# mini.net
KiCad netlist of a schematic drawn in EAGLE
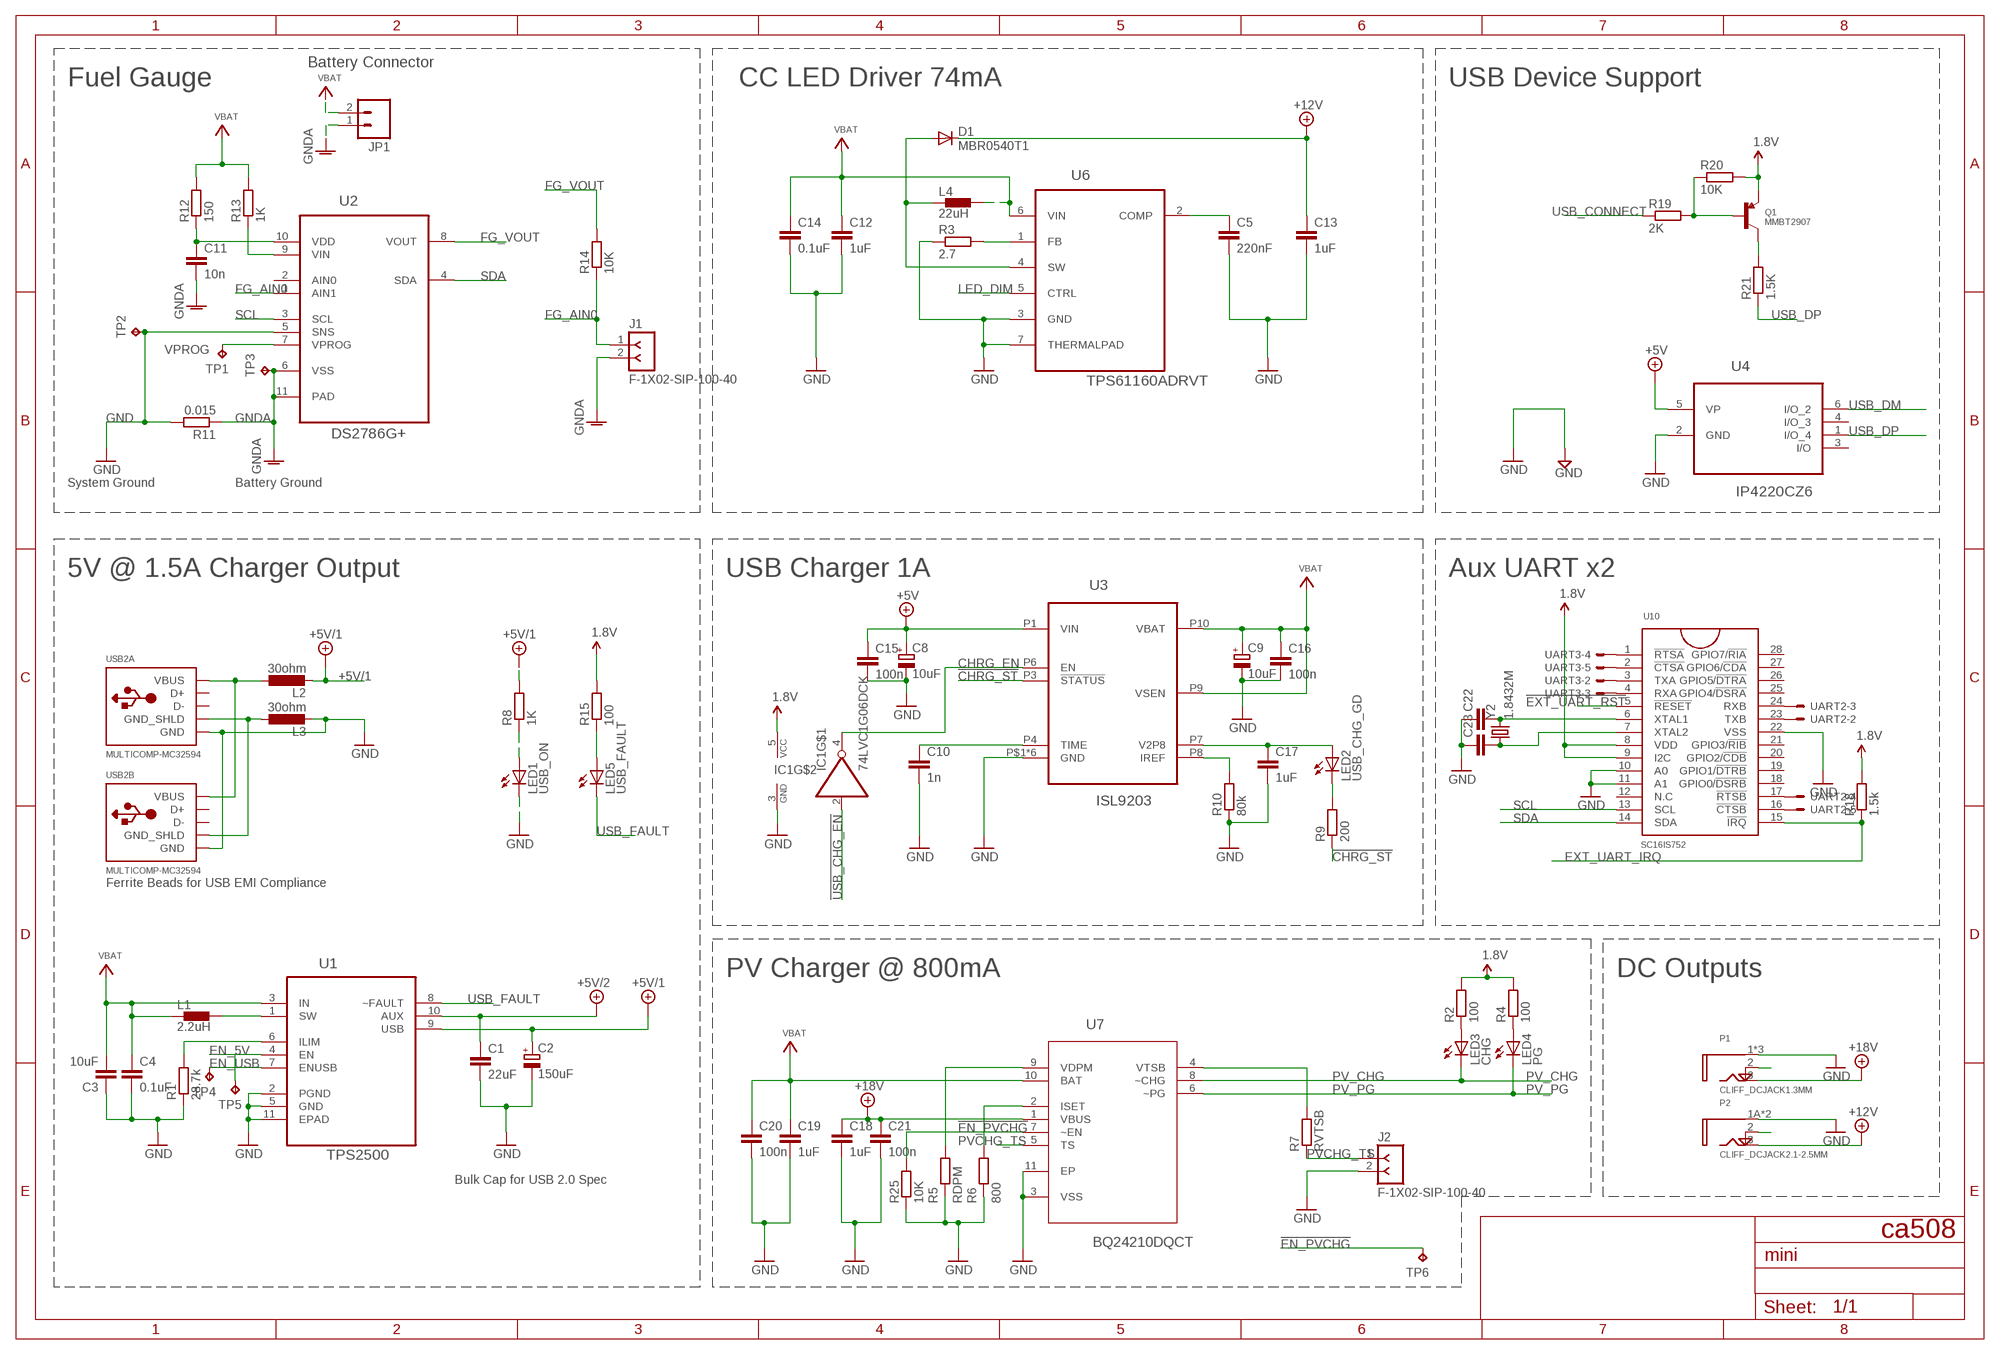
[diagram p0: schematic, sheet 1, part 1 of 2]
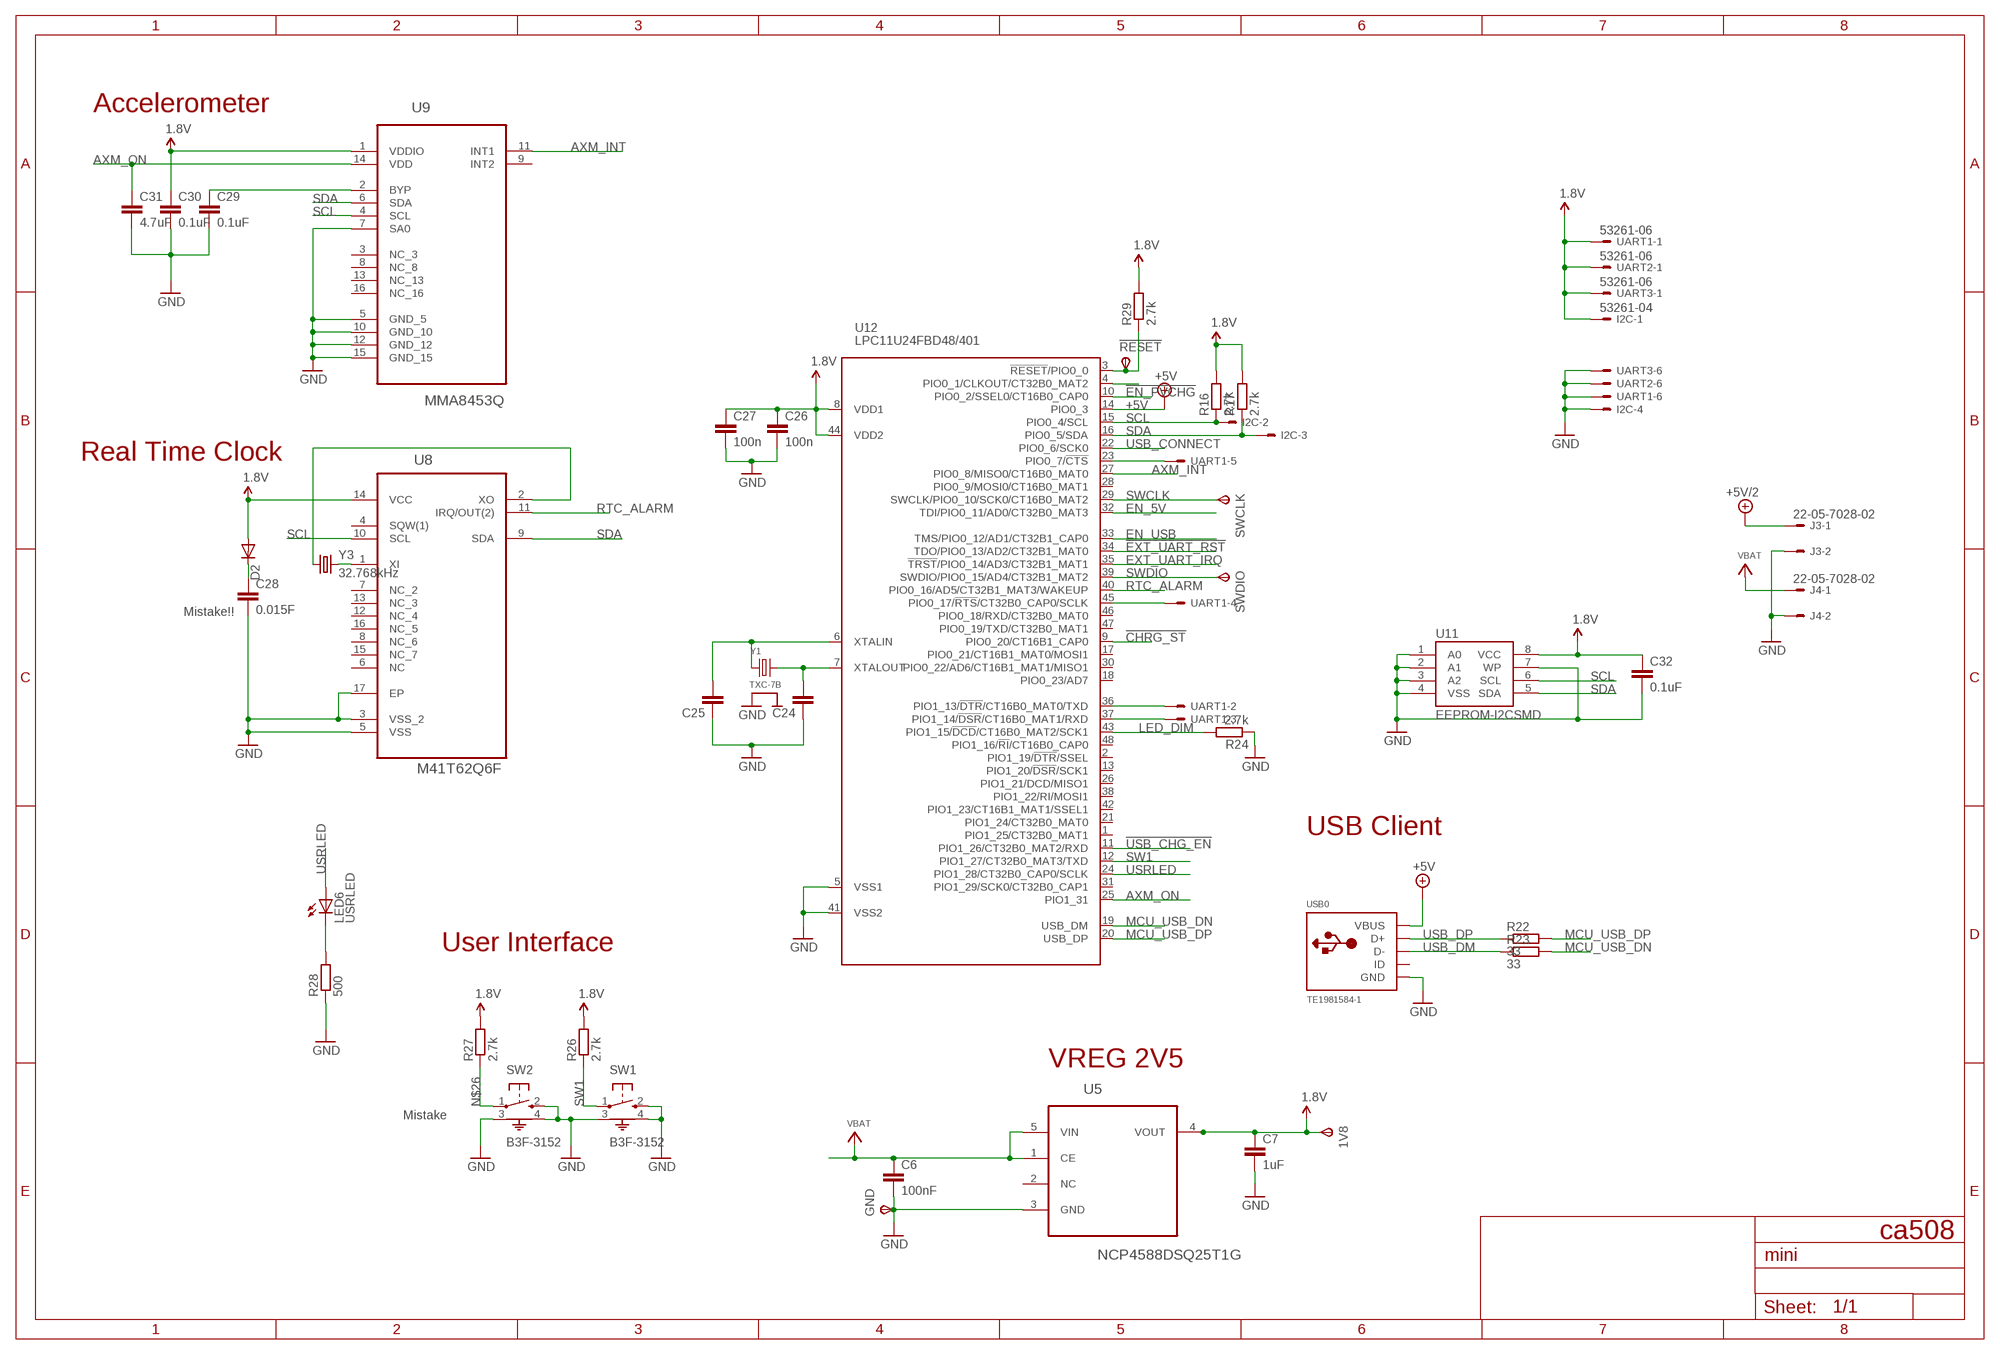
[diagram p1: schematic, sheet 1, part 2 of 2]

(export (version "E")
  (design (tool "Eeschema 10.0.6"))
  (components
    (comp (ref "!RESET!")
      (value "TPSTP13SQ")
      (footprint "eagle-import:TP13SQ")
      (libsource (lib "eagle-import") (part "TPSTP13SQ"))
    )
    (comp (ref "1V8")
      (value "TPSTP13SQ")
      (footprint "eagle-import:TP13SQ")
      (libsource (lib "eagle-import") (part "TPSTP13SQ"))
    )
    (comp (ref "C1")
      (value "22uF")
      (footprint "eagle-import:C1210")
      (libsource (lib "eagle-import") (part "C-EUC1210"))
    )
    (comp (ref "C2")
      (value "150uF")
      (footprint "eagle-import:PANASONIC_D")
      (libsource (lib "eagle-import") (part "CPOL-EUD"))
    )
    (comp (ref "C3")
      (value "10uF")
      (footprint "eagle-import:C0805")
      (libsource (lib "eagle-import") (part "C-EUC0805"))
    )
    (comp (ref "C4")
      (value "0.1uF")
      (footprint "eagle-import:C0603")
      (libsource (lib "eagle-import") (part "C-EUC0603"))
    )
    (comp (ref "C5")
      (value "220nF")
      (footprint "eagle-import:C0603")
      (libsource (lib "eagle-import") (part "C-EUC0603"))
    )
    (comp (ref "C6")
      (value "100nF")
      (footprint "eagle-import:C0805")
      (libsource (lib "eagle-import") (part "C-EUC0805"))
    )
    (comp (ref "C7")
      (value "1uF")
      (footprint "eagle-import:C1206")
      (libsource (lib "eagle-import") (part "C-EUC1206"))
    )
    (comp (ref "C8")
      (value "10uF")
      (footprint "eagle-import:B_3528-21R")
      (libsource (lib "eagle-import") (part "CPOL-EUB/3528-21R"))
    )
    (comp (ref "C9")
      (value "10uF")
      (footprint "eagle-import:B_3528-21R")
      (libsource (lib "eagle-import") (part "CPOL-EUB/3528-21R"))
    )
    (comp (ref "C10")
      (value "1n")
      (footprint "eagle-import:C0603")
      (libsource (lib "eagle-import") (part "C-EUC0603"))
    )
    (comp (ref "C11")
      (value "10n")
      (footprint "eagle-import:C0603")
      (libsource (lib "eagle-import") (part "C-EUC0603"))
    )
    (comp (ref "C12")
      (value "1uF")
      (footprint "eagle-import:C0603")
      (libsource (lib "eagle-import") (part "C-EUC0603"))
    )
    (comp (ref "C13")
      (value "1uF")
      (footprint "eagle-import:C0805")
      (libsource (lib "eagle-import") (part "C-EUC0805"))
    )
    (comp (ref "C14")
      (value "0.1uF")
      (footprint "eagle-import:C0603")
      (libsource (lib "eagle-import") (part "C-EUC0603"))
    )
    (comp (ref "C15")
      (value "100n")
      (footprint "eagle-import:C0603")
      (libsource (lib "eagle-import") (part "C-EUC0603"))
    )
    (comp (ref "C16")
      (value "100n")
      (footprint "eagle-import:C0603")
      (libsource (lib "eagle-import") (part "C-EUC0603"))
    )
    (comp (ref "C17")
      (value "1uF")
      (footprint "eagle-import:C0805")
      (libsource (lib "eagle-import") (part "C-EUC0805"))
    )
    (comp (ref "C18")
      (value "1uF")
      (footprint "eagle-import:C0805")
      (libsource (lib "eagle-import") (part "C-EUC0805"))
    )
    (comp (ref "C19")
      (value "1uF")
      (footprint "eagle-import:C0805")
      (libsource (lib "eagle-import") (part "C-EUC0805"))
    )
    (comp (ref "C20")
      (value "100n")
      (footprint "eagle-import:C0603")
      (libsource (lib "eagle-import") (part "C-EUC0603"))
    )
    (comp (ref "C21")
      (value "100n")
      (footprint "eagle-import:C0603")
      (libsource (lib "eagle-import") (part "C-EUC0603"))
    )
    (comp (ref "C22")
      (value "C-EUC0805")
      (footprint "eagle-import:C0805")
      (libsource (lib "eagle-import") (part "C-EUC0805"))
    )
    (comp (ref "C23")
      (value "C-EUC0805")
      (footprint "eagle-import:C0805")
      (libsource (lib "eagle-import") (part "C-EUC0805"))
    )
    (comp (ref "C24")
      (value "C-EUC0805")
      (footprint "eagle-import:C0805")
      (libsource (lib "eagle-import") (part "C-EUC0805"))
    )
    (comp (ref "C25")
      (value "C-EUC0805")
      (footprint "eagle-import:C0805")
      (libsource (lib "eagle-import") (part "C-EUC0805"))
    )
    (comp (ref "C26")
      (value "100n")
      (footprint "eagle-import:C0603")
      (libsource (lib "eagle-import") (part "C-EUC0603"))
    )
    (comp (ref "C27")
      (value "100n")
      (footprint "eagle-import:C0603")
      (libsource (lib "eagle-import") (part "C-EUC0603"))
    )
    (comp (ref "C28")
      (value "0.015F")
      (footprint "eagle-import:C3225")
      (libsource (lib "eagle-import") (part "C-EUC3225"))
    )
    (comp (ref "C29")
      (value "0.1uF")
      (footprint "eagle-import:C0603")
      (libsource (lib "eagle-import") (part "C-EUC0603"))
    )
    (comp (ref "C30")
      (value "0.1uF")
      (footprint "eagle-import:C0603")
      (libsource (lib "eagle-import") (part "C-EUC0603"))
    )
    (comp (ref "C31")
      (value "4.7uF")
      (footprint "eagle-import:C0805")
      (libsource (lib "eagle-import") (part "C-EUC0805"))
    )
    (comp (ref "C32")
      (value "0.1uF")
      (footprint "eagle-import:C0603")
      (libsource (lib "eagle-import") (part "C-EUC0603"))
    )
    (comp (ref "D1")
      (value "MBR0540T1")
      (footprint "eagle-import:SOD123")
      (libsource (lib "eagle-import") (part "MBR0520LT"))
    )
    (comp (ref "D2")
      (value "DIODE-SOD123")
      (footprint "eagle-import:SOD123")
      (libsource (lib "eagle-import") (part "DIODE-SOD123"))
    )
    (comp (ref "GND")
      (value "TPSTP13SQ")
      (footprint "eagle-import:TP13SQ")
      (libsource (lib "eagle-import") (part "TPSTP13SQ"))
    )
    (comp (ref "I2C")
      (value "53261-04")
      (footprint "eagle-import:53261-04")
      (libsource (lib "eagle-import") (part "53?-04261"))
    )
    (comp (ref "IC1")
      (value "74LVC1G06DCK")
      (footprint "eagle-import:SC70-5")
      (libsource (lib "eagle-import") (part "741G06DCKLVC"))
    )
    (comp (ref "J1")
      (value "F-1X02-SIP-100-40")
      (footprint "eagle-import:SIP-100-02-40")
      (libsource (lib "eagle-import") (part "F-1X02-SIP-100-40"))
    )
    (comp (ref "J2")
      (value "F-1X02-SIP-100-40")
      (footprint "eagle-import:SIP-100-02-40")
      (libsource (lib "eagle-import") (part "F-1X02-SIP-100-40"))
    )
    (comp (ref "J3")
      (value "22-05-7028-02")
      (footprint "eagle-import:7395-02")
      (libsource (lib "eagle-import") (part "22-?-0205-7028"))
    )
    (comp (ref "J4")
      (value "22-05-7028-02")
      (footprint "eagle-import:7395-02")
      (libsource (lib "eagle-import") (part "22-?-0205-7028"))
    )
    (comp (ref "JP1")
      (value "M02-JST-2MM-SMT")
      (footprint "eagle-import:JST-2-SMD")
      (libsource (lib "eagle-import") (part "M02-JST-2MM-SMT"))
    )
    (comp (ref "L1")
      (value "2.2uH")
      (footprint "eagle-import:SDR1006")
      (libsource (lib "eagle-import") (part "SDR1006-XXXKL"))
    )
    (comp (ref "L2")
      (value "30ohm")
      (footprint "eagle-import:L3216C")
      (libsource (lib "eagle-import") (part "L-EUL3216C"))
    )
    (comp (ref "L3")
      (value "30ohm")
      (footprint "eagle-import:L3216C")
      (libsource (lib "eagle-import") (part "L-EUL3216C"))
    )
    (comp (ref "L4")
      (value "22uH")
      (footprint "eagle-import:VLCF-SERIES")
      (libsource (lib "eagle-import") (part "VLCF5020-1"))
    )
    (comp (ref "LED1")
      (value "USB_ON")
      (footprint "eagle-import:CHIP-LED0603")
      (libsource (lib "eagle-import") (part "LEDCHIP-LED0603"))
    )
    (comp (ref "LED2")
      (value "USB_CHG_GD")
      (footprint "eagle-import:CHIP-LED0603")
      (libsource (lib "eagle-import") (part "LEDCHIP-LED0603"))
    )
    (comp (ref "LED3")
      (value "CHG")
      (footprint "eagle-import:CHIP-LED0603")
      (libsource (lib "eagle-import") (part "LEDCHIP-LED0603"))
    )
    (comp (ref "LED4")
      (value "PG")
      (footprint "eagle-import:CHIP-LED0603")
      (libsource (lib "eagle-import") (part "LEDCHIP-LED0603"))
    )
    (comp (ref "LED5")
      (value "USB_FAULT")
      (footprint "eagle-import:CHIP-LED0603")
      (libsource (lib "eagle-import") (part "LEDCHIP-LED0603"))
    )
    (comp (ref "LED6")
      (value "USRLED")
      (footprint "eagle-import:CHIP-LED0603")
      (libsource (lib "eagle-import") (part "LEDCHIP-LED0603"))
    )
    (comp (ref "P1")
      (value "CLIFF_DCJACK1.3MM")
      (footprint "eagle-import:FC68145S")
      (libsource (lib "eagle-import") (part "CLIFF_DCJACK1.3MM"))
    )
    (comp (ref "P2")
      (value "CLIFF_DCJACK2.1-2.5MM")
      (footprint "eagle-import:FC6814XS")
      (libsource (lib "eagle-import") (part "CLIFF_DCJACK2.1-2.5MM"))
    )
    (comp (ref "Q1")
      (value "MMBT2907")
      (footprint "eagle-import:SOT23-R")
      (libsource (lib "eagle-import") (part "TRANSISTOR_PNPSOT23-REFLOW"))
    )
    (comp (ref "R1")
      (value "28.7k")
      (footprint "eagle-import:R0805")
      (libsource (lib "eagle-import") (part "R-EU_R0805"))
    )
    (comp (ref "R2")
      (value "100")
      (footprint "eagle-import:R0603")
      (libsource (lib "eagle-import") (part "R-EU_R0603"))
    )
    (comp (ref "R3")
      (value "2.7")
      (footprint "eagle-import:R0603")
      (libsource (lib "eagle-import") (part "R-EU_R0603"))
    )
    (comp (ref "R4")
      (value "100")
      (footprint "eagle-import:R0603")
      (libsource (lib "eagle-import") (part "R-EU_R0603"))
    )
    (comp (ref "R5")
      (value "RDPM")
      (footprint "eagle-import:R0805")
      (libsource (lib "eagle-import") (part "R-EU_R0805"))
    )
    (comp (ref "R6")
      (value "800")
      (footprint "eagle-import:R0805")
      (libsource (lib "eagle-import") (part "R-EU_R0805"))
    )
    (comp (ref "R7")
      (value "RVTSB")
      (footprint "eagle-import:R0805")
      (libsource (lib "eagle-import") (part "R-EU_R0805"))
    )
    (comp (ref "R8")
      (value "1K")
      (footprint "eagle-import:R0603")
      (libsource (lib "eagle-import") (part "R-EU_R0603"))
    )
    (comp (ref "R9")
      (value "200")
      (footprint "eagle-import:R0603")
      (libsource (lib "eagle-import") (part "R-EU_R0603"))
    )
    (comp (ref "R10")
      (value "80k")
      (footprint "eagle-import:R0805")
      (libsource (lib "eagle-import") (part "R-EU_R0805"))
    )
    (comp (ref "R11")
      (value "0.015")
      (footprint "eagle-import:R2512")
      (libsource (lib "eagle-import") (part "R-EU_R2512"))
    )
    (comp (ref "R12")
      (value "150")
      (footprint "eagle-import:R0805")
      (libsource (lib "eagle-import") (part "R-EU_R0805"))
    )
    (comp (ref "R13")
      (value "1K")
      (footprint "eagle-import:R0805")
      (libsource (lib "eagle-import") (part "R-EU_R0805"))
    )
    (comp (ref "R14")
      (value "10K")
      (footprint "eagle-import:R0805")
      (libsource (lib "eagle-import") (part "R-EU_R0805"))
    )
    (comp (ref "R15")
      (value "100")
      (footprint "eagle-import:R0603")
      (libsource (lib "eagle-import") (part "R-EU_R0603"))
    )
    (comp (ref "R16")
      (value "2.7k")
      (footprint "eagle-import:R0603")
      (libsource (lib "eagle-import") (part "R-EU_R0603"))
    )
    (comp (ref "R17")
      (value "2.7k")
      (footprint "eagle-import:R0603")
      (libsource (lib "eagle-import") (part "R-EU_R0603"))
    )
    (comp (ref "R18")
      (value "1.5k")
      (footprint "eagle-import:R0603")
      (libsource (lib "eagle-import") (part "R-EU_R0603"))
    )
    (comp (ref "R19")
      (value "2K")
      (footprint "eagle-import:R0603")
      (libsource (lib "eagle-import") (part "R-EU_R0603"))
    )
    (comp (ref "R20")
      (value "10K")
      (footprint "eagle-import:R0603")
      (libsource (lib "eagle-import") (part "R-EU_R0603"))
    )
    (comp (ref "R21")
      (value "1.5K")
      (footprint "eagle-import:R0603")
      (libsource (lib "eagle-import") (part "R-EU_R0603"))
    )
    (comp (ref "R22")
      (value "33")
      (footprint "eagle-import:R0603")
      (libsource (lib "eagle-import") (part "R-EU_R0603"))
    )
    (comp (ref "R23")
      (value "33")
      (footprint "eagle-import:R0603")
      (libsource (lib "eagle-import") (part "R-EU_R0603"))
    )
    (comp (ref "R24")
      (value "2.7k")
      (footprint "eagle-import:R0603")
      (libsource (lib "eagle-import") (part "R-EU_R0603"))
    )
    (comp (ref "R25")
      (value "10K")
      (footprint "eagle-import:R0603")
      (libsource (lib "eagle-import") (part "R-EU_R0603"))
    )
    (comp (ref "R26")
      (value "2.7k")
      (footprint "eagle-import:R0603")
      (libsource (lib "eagle-import") (part "R-EU_R0603"))
    )
    (comp (ref "R27")
      (value "2.7k")
      (footprint "eagle-import:R0603")
      (libsource (lib "eagle-import") (part "R-EU_R0603"))
    )
    (comp (ref "R28")
      (value "500")
      (footprint "eagle-import:R0603")
      (libsource (lib "eagle-import") (part "R-EU_R0603"))
    )
    (comp (ref "R29")
      (value "2.7k")
      (footprint "eagle-import:R0603")
      (libsource (lib "eagle-import") (part "R-EU_R0603"))
    )
    (comp (ref "SW1")
      (value "B3F-3152")
      (footprint "eagle-import:B3F-315X")
      (libsource (lib "eagle-import") (part "B3F-3152"))
    )
    (comp (ref "SW2")
      (value "B3F-3152")
      (footprint "eagle-import:B3F-315X")
      (libsource (lib "eagle-import") (part "B3F-3152"))
    )
    (comp (ref "SWCLK")
      (value "TPSTP13SQ")
      (footprint "eagle-import:TP13SQ")
      (libsource (lib "eagle-import") (part "TPSTP13SQ"))
    )
    (comp (ref "SWDIO")
      (value "TPSTP13SQ")
      (footprint "eagle-import:TP13SQ")
      (libsource (lib "eagle-import") (part "TPSTP13SQ"))
    )
    (comp (ref "TP1")
      (value "TPTP14R")
      (footprint "eagle-import:TP14R")
      (libsource (lib "eagle-import") (part "TPTP14R"))
    )
    (comp (ref "TP2")
      (value "TPTP07R")
      (footprint "eagle-import:TP07R")
      (libsource (lib "eagle-import") (part "TPTP07R"))
    )
    (comp (ref "TP3")
      (value "TPTP07R")
      (footprint "eagle-import:TP07R")
      (libsource (lib "eagle-import") (part "TPTP07R"))
    )
    (comp (ref "TP4")
      (value "TPTP07R")
      (footprint "eagle-import:TP07R")
      (libsource (lib "eagle-import") (part "TPTP07R"))
    )
    (comp (ref "TP5")
      (value "TPTP07R")
      (footprint "eagle-import:TP07R")
      (libsource (lib "eagle-import") (part "TPTP07R"))
    )
    (comp (ref "TP6")
      (value "TPTP07R")
      (footprint "eagle-import:TP07R")
      (libsource (lib "eagle-import") (part "TPTP07R"))
    )
    (comp (ref "U1")
      (value "TPS2500")
      (footprint "eagle-import:SON50P300X300X100-11N")
      (fields (field (name "MPN") "TPS2500DRCT"))
      (libsource (lib "eagle-import") (part "TPS2500DRCT"))
    )
    (comp (ref "U2")
      (value "DS2786G+")
      (footprint "eagle-import:DFN300X300X80-11N")
      (libsource (lib "eagle-import") (part "DS2786G+"))
    )
    (comp (ref "U3")
      (value "ISL9203")
      (footprint "eagle-import:INTERSIL_DFN_3X3")
      (libsource (lib "eagle-import") (part "ISL9203"))
    )
    (comp (ref "U4")
      (value "IP4220CZ6")
      (footprint "eagle-import:SOT95P275X110-6N")
      (libsource (lib "eagle-import") (part "IP4220CZ6"))
    )
    (comp (ref "U5")
      (value "NCP4588DSQ25T1G")
      (footprint "eagle-import:SOT65P210X110-5N")
      (libsource (lib "eagle-import") (part "NCP4588DSQ25T1G"))
    )
    (comp (ref "U6")
      (value "TPS61160ADRVT")
      (footprint "eagle-import:SON65P210X210X80-7N")
      (fields (field (name "OC_FARNELL") "1735594") (field (name "OC_NEWARK") "1735594"))
      (libsource (lib "eagle-import") (part "TPS61160ADRVT"))
    )
    (comp (ref "U7")
      (value "BQ24210DQCT")
      (footprint "eagle-import:SON50P200X300X80-11N")
      (libsource (lib "eagle-import") (part "BQ24210DQCT"))
    )
    (comp (ref "U8")
      (value "M41T62Q6F")
      (footprint "eagle-import:QFN50P300X300X100-17N")
      (libsource (lib "eagle-import") (part "M41T62Q6F"))
    )
    (comp (ref "U9")
      (value "MMA8453Q")
      (footprint "eagle-import:QFN50P300X300X100-16N")
      (libsource (lib "eagle-import") (part "MMA8453Q"))
    )
    (comp (ref "U10")
      (value "SC16IS752")
      (footprint "eagle-import:TSSOP28")
      (libsource (lib "eagle-import") (part "SC16IS752"))
    )
    (comp (ref "U11")
      (value "EEPROM-I2CSMD")
      (footprint "eagle-import:SO08")
      (libsource (lib "eagle-import") (part "EEPROM-I2CSMD"))
    )
    (comp (ref "U12")
      (value "LPC11U24FBD48/401")
      (footprint "eagle-import:LQFP48")
      (libsource (lib "eagle-import") (part "LPC11U24FBD48/401"))
    )
    (comp (ref "UART1")
      (value "53261-06")
      (footprint "eagle-import:53261-06")
      (libsource (lib "eagle-import") (part "53?-06261"))
    )
    (comp (ref "UART2")
      (value "53261-06")
      (footprint "eagle-import:53261-06")
      (libsource (lib "eagle-import") (part "53?-06261"))
    )
    (comp (ref "UART3")
      (value "53261-06")
      (footprint "eagle-import:53261-06")
      (libsource (lib "eagle-import") (part "53?-06261"))
    )
    (comp (ref "USB0")
      (value "TE1981584-1")
      (footprint "eagle-import:TE-MICROUSB-AB")
      (libsource (lib "eagle-import") (part "TE1981584-1"))
    )
    (comp (ref "USB2")
      (value "MULTICOMP-MC32594")
      (footprint "eagle-import:MC32594")
      (libsource (lib "eagle-import") (part "MULTICOMP-MC32594"))
    )
    (comp (ref "Y1")
      (value "TXC-7B")
      (footprint "eagle-import:TXC-7B")
      (libsource (lib "eagle-import") (part "TXC-7B"))
    )
    (comp (ref "Y2")
      (value "1.8432M")
      (footprint "eagle-import:HC49U-V")
      (libsource (lib "eagle-import") (part "CRYSTALHC49UV"))
    )
    (comp (ref "Y3")
      (value "32.768kHz")
      (footprint "eagle-import:CRYSTAL-32KHZ-SMD")
      (libsource (lib "eagle-import") (part "CRYSTAL32-SMD"))
    )
  )
  (nets
    (net (code "1") (name "+5V") (class "Default")
      (node (ref "C15") (pin "1") (pinfunction "1_1") (pintype "passive"))
      (node (ref "C8") (pin "+") (pinfunction "+_+") (pintype "passive"))
      (node (ref "U12") (pin "14") (pinfunction "PIO0_3_14") (pintype "bidirectional"))
      (node (ref "U3") (pin "P1") (pinfunction "VIN_P1") (pintype "power_in"))
      (node (ref "U4") (pin "5") (pinfunction "VP_5") (pintype "power_in"))
      (node (ref "USB0") (pin "P1") (pinfunction "VBUS_P1") (pintype "power_in"))
    )
    (net (code "2") (name "+5V{slash}1") (class "Default")
      (node (ref "C2") (pin "+") (pinfunction "+_+") (pintype "passive"))
      (node (ref "L2") (pin "2") (pinfunction "2_2") (pintype "passive"))
      (node (ref "R8") (pin "2") (pinfunction "2_2") (pintype "passive"))
      (node (ref "U1") (pin "9") (pinfunction "USB_9") (pintype "output"))
    )
    (net (code "3") (name "+5V{slash}2") (class "Default")
      (node (ref "C1") (pin "1") (pinfunction "1_1") (pintype "passive"))
      (node (ref "J3") (pin "1") (pinfunction "S_1") (pintype "passive"))
      (node (ref "U1") (pin "10") (pinfunction "AUX_10") (pintype "output"))
    )
    (net (code "4") (name "+12V") (class "Default")
      (node (ref "C13") (pin "1") (pinfunction "1_1") (pintype "passive"))
      (node (ref "D1") (pin "C") (pinfunction "C_C") (pintype "passive"))
      (node (ref "P2") (pin "3") (pinfunction "TIP_3") (pintype "power_in"))
    )
    (net (code "5") (name "+18V") (class "Default")
      (node (ref "C18") (pin "1") (pinfunction "1_1") (pintype "passive"))
      (node (ref "C21") (pin "1") (pinfunction "1_1") (pintype "passive"))
      (node (ref "P1") (pin "3") (pinfunction "TIP_3") (pintype "power_in"))
      (node (ref "U7") (pin "1") (pinfunction "VBUS_1") (pintype "bidirectional"))
    )
    (net (code "6") (name "/AXM_INT") (class "Default")
      (node (ref "U12") (pin "27") (pinfunction "PIO0_8/MISO0/CT16B0_MAT0_27") (pintype "bidirectional"))
      (node (ref "U9") (pin "11") (pinfunction "INT1_11") (pintype "output"))
    )
    (net (code "7") (name "/AXM_ON") (class "Default")
      (node (ref "C31") (pin "1") (pinfunction "1_1") (pintype "passive"))
      (node (ref "U12") (pin "25") (pinfunction "PIO1_31_25") (pintype "bidirectional"))
      (node (ref "U9") (pin "14") (pinfunction "VDD_14") (pintype "power_in"))
    )
    (net (code "8") (name "/CHRG_EN") (class "Default")
      (node (ref "IC1") (pin "4") (pinfunction "O_4") (pintype "open_collector"))
      (node (ref "U3") (pin "P6") (pinfunction "EN_P6") (pintype "input"))
    )
    (net (code "9") (name "/EN_5V") (class "Default")
      (node (ref "TP5") (pin "TP") (pinfunction "TP_TP") (pintype "input"))
      (node (ref "U1") (pin "4") (pinfunction "EN_4") (pintype "input"))
      (node (ref "U12") (pin "32") (pinfunction "TDI/PIO0_11/AD0/CT32B0_MAT3_32") (pintype "bidirectional"))
    )
    (net (code "10") (name "/EN_USB") (class "Default")
      (node (ref "TP4") (pin "TP") (pinfunction "TP_TP") (pintype "input"))
      (node (ref "U1") (pin "7") (pinfunction "ENUSB_7") (pintype "input"))
      (node (ref "U12") (pin "33") (pinfunction "TMS/PIO0_12/AD1/CT32B1_CAP0_33") (pintype "bidirectional"))
    )
    (net (code "11") (name "/EXT_UART_IRQ") (class "Default")
      (node (ref "R18") (pin "1") (pinfunction "1_1") (pintype "passive"))
      (node (ref "U10") (pin "15") (pinfunction "~{IRQ}_15") (pintype "bidirectional"))
      (node (ref "U12") (pin "35") (pinfunction "~{TRST}/PIO0_14/AD3/CT32B1_MAT1_35") (pintype "bidirectional"))
    )
    (net (code "12") (name "/FG_AIN0") (class "Default")
      (node (ref "J1") (pin "1") (pinfunction "1_1") (pintype "passive"))
      (node (ref "R14") (pin "1") (pinfunction "1_1") (pintype "passive"))
      (node (ref "U2") (pin "1") (pinfunction "AIN1_1") (pintype "input"))
    )
    (net (code "13") (name "/FG_VOUT") (class "Default")
      (node (ref "R14") (pin "2") (pinfunction "2_2") (pintype "passive"))
      (node (ref "U2") (pin "8") (pinfunction "VOUT_8") (pintype "output"))
    )
    (net (code "14") (name "/LED_DIM") (class "Default")
      (node (ref "R24") (pin "2") (pinfunction "2_2") (pintype "passive"))
      (node (ref "U12") (pin "43") (pinfunction "PIO1_15/~{DCD}/CT16B0_MAT2/SCK1_43") (pintype "bidirectional"))
      (node (ref "U6") (pin "5") (pinfunction "CTRL_5") (pintype "input"))
    )
    (net (code "15") (name "/MCU_USB_DN") (class "Default")
      (node (ref "R23") (pin "2") (pinfunction "2_2") (pintype "passive"))
      (node (ref "U12") (pin "19") (pinfunction "USB_DM_19") (pintype "bidirectional"))
    )
    (net (code "16") (name "/MCU_USB_DP") (class "Default")
      (node (ref "R22") (pin "2") (pinfunction "2_2") (pintype "passive"))
      (node (ref "U12") (pin "20") (pinfunction "USB_DP_20") (pintype "bidirectional"))
    )
    (net (code "17") (name "/N$26") (class "Default")
      (node (ref "R27") (pin "1") (pinfunction "1_1") (pintype "passive"))
      (node (ref "SW2") (pin "1") (pinfunction "1_1") (pintype "passive"))
    )
    (net (code "18") (name "/PVCHG_TS") (class "Default")
      (node (ref "J2") (pin "1") (pinfunction "1_1") (pintype "passive"))
      (node (ref "R7") (pin "1") (pinfunction "1_1") (pintype "passive"))
      (node (ref "U7") (pin "5") (pinfunction "TS_5") (pintype "input"))
    )
    (net (code "19") (name "/PV_CHG") (class "Default")
      (node (ref "LED3") (pin "C") (pinfunction "C_C") (pintype "passive"))
      (node (ref "U7") (pin "8") (pinfunction "~{CHG}_8") (pintype "output"))
    )
    (net (code "20") (name "/PV_PG") (class "Default")
      (node (ref "LED4") (pin "C") (pinfunction "C_C") (pintype "passive"))
      (node (ref "U7") (pin "6") (pinfunction "~{PG}_6") (pintype "output"))
    )
    (net (code "21") (name "/RTC_ALARM") (class "Default")
      (node (ref "U12") (pin "40") (pinfunction "PIO0_16/AD5/CT32B1_MAT3/WAKEUP_40") (pintype "bidirectional"))
      (node (ref "U8") (pin "11") (pinfunction "IRQ/OUT(2)_11") (pintype "output"))
    )
    (net (code "22") (name "/SCL") (class "Default")
      (node (ref "I2C") (pin "2") (pinfunction "S_2") (pintype "passive"))
      (node (ref "R16") (pin "1") (pinfunction "1_1") (pintype "passive"))
      (node (ref "U10") (pin "13") (pinfunction "SCL_13") (pintype "bidirectional"))
      (node (ref "U11") (pin "6") (pinfunction "SCL_6") (pintype "bidirectional"))
      (node (ref "U12") (pin "15") (pinfunction "PIO0_4/SCL_15") (pintype "bidirectional"))
      (node (ref "U2") (pin "3") (pinfunction "SCL_3") (pintype "input"))
      (node (ref "U8") (pin "10") (pinfunction "SCL_10") (pintype "input"))
      (node (ref "U9") (pin "4") (pinfunction "SCL_4") (pintype "input"))
    )
    (net (code "23") (name "/SDA") (class "Default")
      (node (ref "I2C") (pin "3") (pinfunction "S_3") (pintype "passive"))
      (node (ref "R17") (pin "1") (pinfunction "1_1") (pintype "passive"))
      (node (ref "U10") (pin "14") (pinfunction "SDA_14") (pintype "bidirectional"))
      (node (ref "U11") (pin "5") (pinfunction "SDA_5") (pintype "bidirectional"))
      (node (ref "U12") (pin "16") (pinfunction "PIO0_5/SDA_16") (pintype "bidirectional"))
      (node (ref "U2") (pin "4") (pinfunction "SDA_4") (pintype "output"))
      (node (ref "U8") (pin "9") (pinfunction "SDA_9") (pintype "bidirectional"))
      (node (ref "U9") (pin "6") (pinfunction "SDA_6") (pintype "bidirectional"))
    )
    (net (code "24") (name "/SW1") (class "Default")
      (node (ref "R26") (pin "1") (pinfunction "1_1") (pintype "passive"))
      (node (ref "SW1") (pin "1") (pinfunction "1_1") (pintype "passive"))
      (node (ref "U12") (pin "12") (pinfunction "PIO1_27/CT32B0_MAT3/TXD_12") (pintype "bidirectional"))
    )
    (net (code "25") (name "/SWCLK") (class "Default")
      (node (ref "SWCLK") (pin "TP") (pinfunction "PP_TP") (pintype "input"))
      (node (ref "U12") (pin "29") (pinfunction "SWCLK/PIO0_10/SCK0/CT16B0_MAT2_29") (pintype "bidirectional"))
    )
    (net (code "26") (name "/SWDIO") (class "Default")
      (node (ref "SWDIO") (pin "TP") (pinfunction "PP_TP") (pintype "input"))
      (node (ref "U12") (pin "39") (pinfunction "SWDIO/PIO0_15/AD4/CT32B1_MAT2_39") (pintype "bidirectional"))
    )
    (net (code "27") (name "/USB_CONNECT") (class "Default")
      (node (ref "R19") (pin "1") (pinfunction "1_1") (pintype "passive"))
      (node (ref "U12") (pin "22") (pinfunction "PIO0_6/SCK0_22") (pintype "bidirectional"))
    )
    (net (code "28") (name "/USB_DM") (class "Default")
      (node (ref "R23") (pin "1") (pinfunction "1_1") (pintype "passive"))
      (node (ref "U4") (pin "6") (pinfunction "I/O_2_6") (pintype "bidirectional"))
      (node (ref "USB0") (pin "P2") (pinfunction "D-_P2") (pintype "bidirectional"))
    )
    (net (code "29") (name "/USB_DP") (class "Default")
      (node (ref "R21") (pin "1") (pinfunction "1_1") (pintype "passive"))
      (node (ref "R22") (pin "1") (pinfunction "1_1") (pintype "passive"))
      (node (ref "U4") (pin "1") (pinfunction "I/O_4_1") (pintype "bidirectional"))
      (node (ref "USB0") (pin "P3") (pinfunction "D+_P3") (pintype "bidirectional"))
    )
    (net (code "30") (name "/USB_FAULT") (class "Default")
      (node (ref "LED5") (pin "C") (pinfunction "C_C") (pintype "passive"))
      (node (ref "U1") (pin "8") (pinfunction "~{FAULT}_8") (pintype "output"))
    )
    (net (code "31") (name "/USRLED") (class "Default")
      (node (ref "LED6") (pin "A") (pinfunction "A_A") (pintype "passive"))
      (node (ref "U12") (pin "24") (pinfunction "PIO1_28/CT32B0_CAP0/SCLK_24") (pintype "bidirectional"))
    )
    (net (code "32") (name "/VPROG") (class "Default")
      (node (ref "TP1") (pin "TP") (pinfunction "TP_TP") (pintype "input"))
      (node (ref "U2") (pin "7") (pinfunction "VPROG_7") (pintype "power_in"))
    )
    (net (code "33") (name "/~{CHRG_ST}") (class "Default")
      (node (ref "R9") (pin "1") (pinfunction "1_1") (pintype "passive"))
      (node (ref "U12") (pin "9") (pinfunction "PIO0_20/CT16B1_CAP0_9") (pintype "bidirectional"))
      (node (ref "U3") (pin "P3") (pinfunction "~{STATUS}_P3") (pintype "output"))
    )
    (net (code "34") (name "/~{EN_PVCHG}") (class "Default")
      (node (ref "R25") (pin "2") (pinfunction "2_2") (pintype "passive"))
      (node (ref "TP6") (pin "TP") (pinfunction "TP_TP") (pintype "input"))
      (node (ref "U12") (pin "10") (pinfunction "PIO0_2/SSEL0/CT16B0_CAP0_10") (pintype "bidirectional"))
      (node (ref "U7") (pin "7") (pinfunction "~{EN}_7") (pintype "input"))
    )
    (net (code "35") (name "/~{EXT_UART_RST}") (class "Default")
      (node (ref "U10") (pin "5") (pinfunction "~{RESET}_5") (pintype "bidirectional"))
      (node (ref "U12") (pin "34") (pinfunction "TDO/PIO0_13/AD2/CT32B1_MAT0_34") (pintype "bidirectional"))
    )
    (net (code "36") (name "/~{USB_CHG_EN}") (class "Default")
      (node (ref "IC1") (pin "2") (pinfunction "I_2") (pintype "input"))
      (node (ref "U12") (pin "11") (pinfunction "PIO1_26/CT32B0_MAT2/RXD_11") (pintype "bidirectional"))
    )
    (net (code "37") (name "1.8V") (class "Default")
      (node (ref "1V8") (pin "TP") (pinfunction "PP_TP") (pintype "input"))
      (node (ref "C26") (pin "1") (pinfunction "1_1") (pintype "passive"))
      (node (ref "C27") (pin "1") (pinfunction "1_1") (pintype "passive"))
      (node (ref "C30") (pin "1") (pinfunction "1_1") (pintype "passive"))
      (node (ref "C32") (pin "1") (pinfunction "1_1") (pintype "passive"))
      (node (ref "C7") (pin "1") (pinfunction "1_1") (pintype "passive"))
      (node (ref "D2") (pin "A") (pinfunction "A_A") (pintype "passive"))
      (node (ref "I2C") (pin "1") (pinfunction "S_1") (pintype "passive"))
      (node (ref "IC1") (pin "5") (pinfunction "VCC_5") (pintype "power_in"))
      (node (ref "Q1") (pin "2") (pinfunction "E_2") (pintype "passive"))
      (node (ref "R15") (pin "2") (pinfunction "2_2") (pintype "passive"))
      (node (ref "R16") (pin "2") (pinfunction "2_2") (pintype "passive"))
      (node (ref "R17") (pin "2") (pinfunction "2_2") (pintype "passive"))
      (node (ref "R18") (pin "2") (pinfunction "2_2") (pintype "passive"))
      (node (ref "R2") (pin "2") (pinfunction "2_2") (pintype "passive"))
      (node (ref "R20") (pin "2") (pinfunction "2_2") (pintype "passive"))
      (node (ref "R26") (pin "2") (pinfunction "2_2") (pintype "passive"))
      (node (ref "R27") (pin "2") (pinfunction "2_2") (pintype "passive"))
      (node (ref "R29") (pin "2") (pinfunction "2_2") (pintype "passive"))
      (node (ref "R4") (pin "2") (pinfunction "2_2") (pintype "passive"))
      (node (ref "U10") (pin "8") (pinfunction "VDD_8") (pintype "bidirectional"))
      (node (ref "U10") (pin "9") (pinfunction "I2C_9") (pintype "bidirectional"))
      (node (ref "U11") (pin "8") (pinfunction "VCC_8") (pintype "power_in"))
      (node (ref "U12") (pin "44") (pinfunction "VDD2_44") (pintype "power_in"))
      (node (ref "U12") (pin "8") (pinfunction "VDD1_8") (pintype "power_in"))
      (node (ref "U5") (pin "4") (pinfunction "VOUT_4") (pintype "output"))
      (node (ref "U8") (pin "14") (pinfunction "VCC_14") (pintype "power_in"))
      (node (ref "U9") (pin "1") (pinfunction "VDDIO_1") (pintype "power_in"))
      (node (ref "UART1") (pin "1") (pinfunction "S_1") (pintype "passive"))
      (node (ref "UART2") (pin "1") (pinfunction "S_1") (pintype "passive"))
      (node (ref "UART3") (pin "1") (pinfunction "S_1") (pintype "passive"))
    )
    (net (code "38") (name "GND") (class "Default")
      (node (ref "C1") (pin "2") (pinfunction "2_2") (pintype "passive"))
      (node (ref "C10") (pin "2") (pinfunction "2_2") (pintype "passive"))
      (node (ref "C12") (pin "2") (pinfunction "2_2") (pintype "passive"))
      (node (ref "C13") (pin "2") (pinfunction "2_2") (pintype "passive"))
      (node (ref "C14") (pin "2") (pinfunction "2_2") (pintype "passive"))
      (node (ref "C15") (pin "2") (pinfunction "2_2") (pintype "passive"))
      (node (ref "C16") (pin "2") (pinfunction "2_2") (pintype "passive"))
      (node (ref "C17") (pin "2") (pinfunction "2_2") (pintype "passive"))
      (node (ref "C18") (pin "2") (pinfunction "2_2") (pintype "passive"))
      (node (ref "C19") (pin "2") (pinfunction "2_2") (pintype "passive"))
      (node (ref "C2") (pin "-") (pinfunction "-_-") (pintype "passive"))
      (node (ref "C20") (pin "2") (pinfunction "2_2") (pintype "passive"))
      (node (ref "C21") (pin "2") (pinfunction "2_2") (pintype "passive"))
      (node (ref "C22") (pin "1") (pinfunction "1_1") (pintype "passive"))
      (node (ref "C23") (pin "1") (pinfunction "1_1") (pintype "passive"))
      (node (ref "C24") (pin "1") (pinfunction "1_1") (pintype "passive"))
      (node (ref "C25") (pin "1") (pinfunction "1_1") (pintype "passive"))
      (node (ref "C26") (pin "2") (pinfunction "2_2") (pintype "passive"))
      (node (ref "C27") (pin "2") (pinfunction "2_2") (pintype "passive"))
      (node (ref "C28") (pin "2") (pinfunction "2_2") (pintype "passive"))
      (node (ref "C29") (pin "2") (pinfunction "2_2") (pintype "passive"))
      (node (ref "C3") (pin "1") (pinfunction "1_1") (pintype "passive"))
      (node (ref "C30") (pin "2") (pinfunction "2_2") (pintype "passive"))
      (node (ref "C31") (pin "2") (pinfunction "2_2") (pintype "passive"))
      (node (ref "C32") (pin "2") (pinfunction "2_2") (pintype "passive"))
      (node (ref "C4") (pin "2") (pinfunction "2_2") (pintype "passive"))
      (node (ref "C5") (pin "2") (pinfunction "2_2") (pintype "passive"))
      (node (ref "C6") (pin "2") (pinfunction "2_2") (pintype "passive"))
      (node (ref "C7") (pin "2") (pinfunction "2_2") (pintype "passive"))
      (node (ref "C8") (pin "-") (pinfunction "-_-") (pintype "passive"))
      (node (ref "C9") (pin "-") (pinfunction "-_-") (pintype "passive"))
      (node (ref "GND") (pin "TP") (pinfunction "PP_TP") (pintype "input"))
      (node (ref "I2C") (pin "4") (pinfunction "S_4") (pintype "passive"))
      (node (ref "IC1") (pin "3") (pinfunction "GND_3") (pintype "power_in"))
      (node (ref "J2") (pin "2") (pinfunction "2_2") (pintype "passive"))
      (node (ref "J3") (pin "2") (pinfunction "S_2") (pintype "passive"))
      (node (ref "J4") (pin "2") (pinfunction "S_2") (pintype "passive"))
      (node (ref "L3") (pin "2") (pinfunction "2_2") (pintype "passive"))
      (node (ref "LED1") (pin "C") (pinfunction "C_C") (pintype "passive"))
      (node (ref "P1") (pin "1") (pinfunction "SLEEVE_1") (pintype "power_in"))
      (node (ref "P1") (pin "4A") (pinfunction "SLEEVE_4A") (pintype "power_in"))
      (node (ref "P1") (pin "4B") (pinfunction "SLEEVE_4B") (pintype "power_in"))
      (node (ref "P2") (pin "1A") (pinfunction "SLEEVE_1A") (pintype "power_in"))
      (node (ref "P2") (pin "1B") (pinfunction "SLEEVE_1B") (pintype "power_in"))
      (node (ref "R1") (pin "1") (pinfunction "1_1") (pintype "passive"))
      (node (ref "R10") (pin "1") (pinfunction "1_1") (pintype "passive"))
      (node (ref "R11") (pin "2") (pinfunction "2_2") (pintype "passive"))
      (node (ref "R24") (pin "1") (pinfunction "1_1") (pintype "passive"))
      (node (ref "R25") (pin "1") (pinfunction "1_1") (pintype "passive"))
      (node (ref "R28") (pin "1") (pinfunction "1_1") (pintype "passive"))
      (node (ref "R3") (pin "1") (pinfunction "1_1") (pintype "passive"))
      (node (ref "R5") (pin "1") (pinfunction "1_1") (pintype "passive"))
      (node (ref "R6") (pin "1") (pinfunction "1_1") (pintype "passive"))
      (node (ref "SW1") (pin "2") (pinfunction "3_2") (pintype "passive"))
      (node (ref "SW1") (pin "3") (pinfunction "2_3") (pintype "passive"))
      (node (ref "SW1") (pin "4") (pinfunction "4_4") (pintype "passive"))
      (node (ref "SW2") (pin "2") (pinfunction "3_2") (pintype "passive"))
      (node (ref "SW2") (pin "3") (pinfunction "2_3") (pintype "passive"))
      (node (ref "SW2") (pin "4") (pinfunction "4_4") (pintype "passive"))
      (node (ref "TP2") (pin "TP") (pinfunction "TP_TP") (pintype "input"))
      (node (ref "U1") (pin "11") (pinfunction "EPAD_11") (pintype "passive"))
      (node (ref "U1") (pin "2") (pinfunction "PGND_2") (pintype "passive"))
      (node (ref "U1") (pin "5") (pinfunction "GND_5") (pintype "passive"))
      (node (ref "U10") (pin "10") (pinfunction "A0_10") (pintype "input"))
      (node (ref "U10") (pin "11") (pinfunction "A1_11") (pintype "bidirectional"))
      (node (ref "U10") (pin "22") (pinfunction "VSS_22") (pintype "bidirectional"))
      (node (ref "U11") (pin "1") (pinfunction "A0_1") (pintype "bidirectional"))
      (node (ref "U11") (pin "2") (pinfunction "A1_2") (pintype "bidirectional"))
      (node (ref "U11") (pin "3") (pinfunction "A2_3") (pintype "bidirectional"))
      (node (ref "U11") (pin "4") (pinfunction "VSS_4") (pintype "power_in"))
      (node (ref "U11") (pin "7") (pinfunction "WP_7") (pintype "bidirectional"))
      (node (ref "U12") (pin "41") (pinfunction "VSS2_41") (pintype "power_in"))
      (node (ref "U12") (pin "5") (pinfunction "VSS1_5") (pintype "power_in"))
      (node (ref "U2") (pin "5") (pinfunction "SNS_5") (pintype "input"))
      (node (ref "U3") (pin "P$1") (pinfunction "GND_P$1") (pintype "passive"))
      (node (ref "U3") (pin "P$2") (pinfunction "GND_P$2") (pintype "passive"))
      (node (ref "U3") (pin "P$3") (pinfunction "GND_P$3") (pintype "passive"))
      (node (ref "U3") (pin "P$4") (pinfunction "GND_P$4") (pintype "passive"))
      (node (ref "U3") (pin "P5") (pinfunction "GND_P5") (pintype "passive"))
      (node (ref "U3") (pin "PAD") (pinfunction "GND_PAD") (pintype "passive"))
      (node (ref "U4") (pin "2") (pinfunction "GND_2") (pintype "passive"))
      (node (ref "U5") (pin "3") (pinfunction "GND_3") (pintype "passive"))
      (node (ref "U6") (pin "3") (pinfunction "GND_3") (pintype "passive"))
      (node (ref "U6") (pin "7") (pinfunction "THERMALPAD_7") (pintype "passive"))
      (node (ref "U7") (pin "11") (pinfunction "EP_11") (pintype "passive"))
      (node (ref "U7") (pin "3") (pinfunction "VSS_3") (pintype "passive"))
      (node (ref "U8") (pin "17") (pinfunction "EP_17") (pintype "passive"))
      (node (ref "U8") (pin "3") (pinfunction "VSS_2_3") (pintype "passive"))
      (node (ref "U8") (pin "5") (pinfunction "VSS_5") (pintype "passive"))
      (node (ref "U9") (pin "10") (pinfunction "GND_10_10") (pintype "passive"))
      (node (ref "U9") (pin "12") (pinfunction "GND_12_12") (pintype "passive"))
      (node (ref "U9") (pin "15") (pinfunction "GND_15_15") (pintype "passive"))
      (node (ref "U9") (pin "5") (pinfunction "GND_5_5") (pintype "passive"))
      (node (ref "U9") (pin "7") (pinfunction "SA0_7") (pintype "input"))
      (node (ref "UART1") (pin "6") (pinfunction "S_6") (pintype "passive"))
      (node (ref "UART2") (pin "6") (pinfunction "S_6") (pintype "passive"))
      (node (ref "UART3") (pin "6") (pinfunction "S_6") (pintype "passive"))
      (node (ref "USB0") (pin "P5") (pinfunction "GND_P5") (pintype "power_in"))
      (node (ref "USB2") (pin "USB1-4") (pinfunction "GND_USB1-4") (pintype "power_in"))
      (node (ref "USB2") (pin "USB2-4") (pinfunction "GND_USB2-4") (pintype "power_in"))
      (node (ref "Y1") (pin "2") (pinfunction "4_2") (pintype "passive"))
      (node (ref "Y1") (pin "4") (pinfunction "4_4") (pintype "passive"))
    )
    (net (code "39") (name "GNDA") (class "Default")
      (node (ref "C11") (pin "2") (pinfunction "2_2") (pintype "passive"))
      (node (ref "J1") (pin "2") (pinfunction "2_2") (pintype "passive"))
      (node (ref "JP1") (pin "1") (pinfunction "2_1") (pintype "passive"))
      (node (ref "R11") (pin "1") (pinfunction "1_1") (pintype "passive"))
      (node (ref "TP3") (pin "TP") (pinfunction "TP_TP") (pintype "input"))
      (node (ref "U2") (pin "11") (pinfunction "PAD_11") (pintype "passive"))
      (node (ref "U2") (pin "6") (pinfunction "VSS_6") (pintype "passive"))
    )
    (net (code "40") (name "Net-(!RESET!-PP)") (class "Default")
      (node (ref "!RESET!") (pin "TP") (pinfunction "PP_TP") (pintype "input"))
      (node (ref "R29") (pin "1") (pinfunction "1_1") (pintype "passive"))
      (node (ref "U12") (pin "3") (pinfunction "~{RESET}/PIO0_0_3") (pintype "bidirectional"))
    )
    (net (code "41") (name "Net-(C28-Pad1)") (class "Default")
      (node (ref "C28") (pin "1") (pinfunction "1_1") (pintype "passive"))
      (node (ref "D2") (pin "C") (pinfunction "C_C") (pintype "passive"))
    )
    (net (code "42") (name "Net-(L1-2)") (class "Default")
      (node (ref "L1") (pin "P$2") (pinfunction "2_P$2") (pintype "passive"))
      (node (ref "U1") (pin "1") (pinfunction "SW_1") (pintype "power_in"))
    )
    (net (code "43") (name "Net-(L3-Pad1)") (class "Default")
      (node (ref "L3") (pin "1") (pinfunction "1_1") (pintype "passive"))
      (node (ref "USB2") (pin "P$1") (pinfunction "GND_SHLD_P$1") (pintype "power_in"))
      (node (ref "USB2") (pin "P$2") (pinfunction "GND_SHLD_P$2") (pintype "power_in"))
      (node (ref "USB2") (pin "P$3") (pinfunction "GND_SHLD_P$3") (pintype "power_in"))
      (node (ref "USB2") (pin "P$4") (pinfunction "GND_SHLD_P$4") (pintype "power_in"))
    )
    (net (code "44") (name "Net-(LED1-PadA)") (class "Default")
      (node (ref "LED1") (pin "A") (pinfunction "A_A") (pintype "passive"))
      (node (ref "R8") (pin "1") (pinfunction "1_1") (pintype "passive"))
    )
    (net (code "45") (name "Net-(LED2-PadC)") (class "Default")
      (node (ref "LED2") (pin "C") (pinfunction "C_C") (pintype "passive"))
      (node (ref "R9") (pin "2") (pinfunction "2_2") (pintype "passive"))
    )
    (net (code "46") (name "Net-(LED3-PadA)") (class "Default")
      (node (ref "LED3") (pin "A") (pinfunction "A_A") (pintype "passive"))
      (node (ref "R2") (pin "1") (pinfunction "1_1") (pintype "passive"))
    )
    (net (code "47") (name "Net-(LED4-PadA)") (class "Default")
      (node (ref "LED4") (pin "A") (pinfunction "A_A") (pintype "passive"))
      (node (ref "R4") (pin "1") (pinfunction "1_1") (pintype "passive"))
    )
    (net (code "48") (name "Net-(LED5-PadA)") (class "Default")
      (node (ref "LED5") (pin "A") (pinfunction "A_A") (pintype "passive"))
      (node (ref "R15") (pin "1") (pinfunction "1_1") (pintype "passive"))
    )
    (net (code "49") (name "Net-(LED6-PadC)") (class "Default")
      (node (ref "LED6") (pin "C") (pinfunction "C_C") (pintype "passive"))
      (node (ref "R28") (pin "2") (pinfunction "2_2") (pintype "passive"))
    )
    (net (code "50") (name "Net-(Q1-B)") (class "Default")
      (node (ref "Q1") (pin "1") (pinfunction "B_1") (pintype "passive"))
      (node (ref "R19") (pin "2") (pinfunction "2_2") (pintype "passive"))
      (node (ref "R20") (pin "1") (pinfunction "1_1") (pintype "passive"))
    )
    (net (code "51") (name "Net-(Q1-C)") (class "Default")
      (node (ref "Q1") (pin "3") (pinfunction "C_3") (pintype "passive"))
      (node (ref "R21") (pin "2") (pinfunction "2_2") (pintype "passive"))
    )
    (net (code "52") (name "Net-(U1-ILIM)") (class "Default")
      (node (ref "R1") (pin "2") (pinfunction "2_2") (pintype "passive"))
      (node (ref "U1") (pin "6") (pinfunction "ILIM_6") (pintype "input"))
    )
    (net (code "53") (name "Net-(U2-VDD)") (class "Default")
      (node (ref "C11") (pin "1") (pinfunction "1_1") (pintype "passive"))
      (node (ref "R12") (pin "1") (pinfunction "1_1") (pintype "passive"))
      (node (ref "U2") (pin "10") (pinfunction "VDD_10") (pintype "power_in"))
    )
    (net (code "54") (name "Net-(U2-VIN)") (class "Default")
      (node (ref "R13") (pin "1") (pinfunction "1_1") (pintype "passive"))
      (node (ref "U2") (pin "9") (pinfunction "VIN_9") (pintype "input"))
    )
    (net (code "55") (name "Net-(U3-IREF)") (class "Default")
      (node (ref "R10") (pin "2") (pinfunction "2_2") (pintype "passive"))
      (node (ref "U3") (pin "P8") (pinfunction "IREF_P8") (pintype "input"))
    )
    (net (code "56") (name "Net-(U3-TIME)") (class "Default")
      (node (ref "C10") (pin "1") (pinfunction "1_1") (pintype "passive"))
      (node (ref "U3") (pin "P4") (pinfunction "TIME_P4") (pintype "input"))
    )
    (net (code "57") (name "Net-(U3-V2P8)") (class "Default")
      (node (ref "C17") (pin "1") (pinfunction "1_1") (pintype "passive"))
      (node (ref "LED2") (pin "A") (pinfunction "A_A") (pintype "passive"))
      (node (ref "U3") (pin "P7") (pinfunction "V2P8_P7") (pintype "output"))
    )
    (net (code "58") (name "Net-(U6-COMP)") (class "Default")
      (node (ref "C5") (pin "1") (pinfunction "1_1") (pintype "passive"))
      (node (ref "U6") (pin "2") (pinfunction "COMP_2") (pintype "output"))
    )
    (net (code "59") (name "Net-(U6-FB)") (class "Default")
      (node (ref "R3") (pin "2") (pinfunction "2_2") (pintype "passive"))
      (node (ref "U6") (pin "1") (pinfunction "FB_1") (pintype "input"))
    )
    (net (code "60") (name "Net-(U6-SW)") (class "Default")
      (node (ref "D1") (pin "A") (pinfunction "A_A") (pintype "passive"))
      (node (ref "L4") (pin "1") (pinfunction "1_1") (pintype "passive"))
      (node (ref "U6") (pin "4") (pinfunction "SW_4") (pintype "input"))
    )
    (net (code "61") (name "Net-(U7-ISET)") (class "Default")
      (node (ref "R6") (pin "2") (pinfunction "2_2") (pintype "passive"))
      (node (ref "U7") (pin "2") (pinfunction "ISET_2") (pintype "input"))
    )
    (net (code "62") (name "Net-(U7-VDPM)") (class "Default")
      (node (ref "R5") (pin "2") (pinfunction "2_2") (pintype "passive"))
      (node (ref "U7") (pin "9") (pinfunction "VDPM_9") (pintype "input"))
    )
    (net (code "63") (name "Net-(U7-VTSB)") (class "Default")
      (node (ref "R7") (pin "2") (pinfunction "2_2") (pintype "passive"))
      (node (ref "U7") (pin "4") (pinfunction "VTSB_4") (pintype "output"))
    )
    (net (code "64") (name "Net-(U8-XI)") (class "Default")
      (node (ref "U8") (pin "1") (pinfunction "XI_1") (pintype "input"))
      (node (ref "Y3") (pin "X2") (pinfunction "2_X2") (pintype "passive"))
    )
    (net (code "65") (name "Net-(U8-XO)") (class "Default")
      (node (ref "U8") (pin "2") (pinfunction "XO_2") (pintype "output"))
      (node (ref "Y3") (pin "X1") (pinfunction "1_X1") (pintype "passive"))
    )
    (net (code "66") (name "Net-(U9-BYP)") (class "Default")
      (node (ref "C29") (pin "1") (pinfunction "1_1") (pintype "passive"))
      (node (ref "U9") (pin "2") (pinfunction "BYP_2") (pintype "input"))
    )
    (net (code "67") (name "Net-(U10-RXA)") (class "Default")
      (node (ref "U10") (pin "4") (pinfunction "RXA_4") (pintype "bidirectional"))
      (node (ref "UART3") (pin "3") (pinfunction "S_3") (pintype "passive"))
    )
    (net (code "68") (name "Net-(U10-RXB)") (class "Default")
      (node (ref "U10") (pin "24") (pinfunction "RXB_24") (pintype "bidirectional"))
      (node (ref "UART2") (pin "3") (pinfunction "S_3") (pintype "passive"))
    )
    (net (code "69") (name "Net-(U10-TXA)") (class "Default")
      (node (ref "U10") (pin "3") (pinfunction "TXA_3") (pintype "input"))
      (node (ref "UART3") (pin "2") (pinfunction "S_2") (pintype "passive"))
    )
    (net (code "70") (name "Net-(U10-TXB)") (class "Default")
      (node (ref "U10") (pin "23") (pinfunction "TXB_23") (pintype "bidirectional"))
      (node (ref "UART2") (pin "2") (pinfunction "S_2") (pintype "passive"))
    )
    (net (code "71") (name "Net-(U10-XTAL1)") (class "Default")
      (node (ref "C22") (pin "2") (pinfunction "2_2") (pintype "passive"))
      (node (ref "U10") (pin "6") (pinfunction "XTAL1_6") (pintype "bidirectional"))
      (node (ref "Y2") (pin "2") (pinfunction "2_2") (pintype "passive"))
    )
    (net (code "72") (name "Net-(U10-XTAL2)") (class "Default")
      (node (ref "C23") (pin "2") (pinfunction "2_2") (pintype "passive"))
      (node (ref "U10") (pin "7") (pinfunction "XTAL2_7") (pintype "bidirectional"))
      (node (ref "Y2") (pin "1") (pinfunction "1_1") (pintype "passive"))
    )
    (net (code "73") (name "Net-(U10-~{CTSA})") (class "Default")
      (node (ref "U10") (pin "2") (pinfunction "~{CTSA}_2") (pintype "input"))
      (node (ref "UART3") (pin "5") (pinfunction "S_5") (pintype "passive"))
    )
    (net (code "74") (name "Net-(U10-~{CTSB})") (class "Default")
      (node (ref "U10") (pin "16") (pinfunction "~{CTSB}_16") (pintype "bidirectional"))
      (node (ref "UART2") (pin "5") (pinfunction "S_5") (pintype "passive"))
    )
    (net (code "75") (name "Net-(U10-~{RTSA})") (class "Default")
      (node (ref "U10") (pin "1") (pinfunction "~{RTSA}_1") (pintype "input"))
      (node (ref "UART3") (pin "4") (pinfunction "S_4") (pintype "passive"))
    )
    (net (code "76") (name "Net-(U10-~{RTSB})") (class "Default")
      (node (ref "U10") (pin "17") (pinfunction "~{RTSB}_17") (pintype "bidirectional"))
      (node (ref "UART2") (pin "4") (pinfunction "S_4") (pintype "passive"))
    )
    (net (code "77") (name "Net-(U12-PIO0_7{slash}~{CTS})") (class "Default")
      (node (ref "U12") (pin "23") (pinfunction "PIO0_7/~{CTS}_23") (pintype "bidirectional"))
      (node (ref "UART1") (pin "5") (pinfunction "S_5") (pintype "passive"))
    )
    (net (code "78") (name "Net-(U12-PIO0_17{slash}~{RTS}{slash}CT32B0_CAP0{slash}SCLK)") (class "Default")
      (node (ref "U12") (pin "45") (pinfunction "PIO0_17/~{RTS}/CT32B0_CAP0/SCLK_45") (pintype "bidirectional"))
      (node (ref "UART1") (pin "4") (pinfunction "S_4") (pintype "passive"))
    )
    (net (code "79") (name "Net-(U12-PIO1_13{slash}~{DTR}{slash}CT16B0_MAT0{slash}TXD)") (class "Default")
      (node (ref "U12") (pin "36") (pinfunction "PIO1_13/~{DTR}/CT16B0_MAT0/TXD_36") (pintype "bidirectional"))
      (node (ref "UART1") (pin "2") (pinfunction "S_2") (pintype "passive"))
    )
    (net (code "80") (name "Net-(U12-PIO1_14{slash}~{DSR}{slash}CT16B0_MAT1{slash}RXD)") (class "Default")
      (node (ref "U12") (pin "37") (pinfunction "PIO1_14/~{DSR}/CT16B0_MAT1/RXD_37") (pintype "bidirectional"))
      (node (ref "UART1") (pin "3") (pinfunction "S_3") (pintype "passive"))
    )
    (net (code "81") (name "Net-(U12-XTALIN)") (class "Default")
      (node (ref "C25") (pin "2") (pinfunction "2_2") (pintype "passive"))
      (node (ref "U12") (pin "6") (pinfunction "XTALIN_6") (pintype "passive"))
      (node (ref "Y1") (pin "1") (pinfunction "1_1") (pintype "passive"))
    )
    (net (code "82") (name "Net-(U12-XTALOUT)") (class "Default")
      (node (ref "C24") (pin "2") (pinfunction "2_2") (pintype "passive"))
      (node (ref "U12") (pin "7") (pinfunction "XTALOUT_7") (pintype "passive"))
      (node (ref "Y1") (pin "3") (pinfunction "2_3") (pintype "passive"))
    )
    (net (code "83") (name "Net-(USB2A-VBUS)") (class "Default")
      (node (ref "L2") (pin "1") (pinfunction "1_1") (pintype "passive"))
      (node (ref "USB2") (pin "USB1-1") (pinfunction "VBUS_USB1-1") (pintype "power_in"))
      (node (ref "USB2") (pin "USB2-1") (pinfunction "VBUS_USB2-1") (pintype "power_in"))
    )
    (net (code "84") (name "VBAT") (class "Default")
      (node (ref "C12") (pin "1") (pinfunction "1_1") (pintype "passive"))
      (node (ref "C14") (pin "1") (pinfunction "1_1") (pintype "passive"))
      (node (ref "C16") (pin "1") (pinfunction "1_1") (pintype "passive"))
      (node (ref "C19") (pin "1") (pinfunction "1_1") (pintype "passive"))
      (node (ref "C20") (pin "1") (pinfunction "1_1") (pintype "passive"))
      (node (ref "C3") (pin "2") (pinfunction "2_2") (pintype "passive"))
      (node (ref "C4") (pin "1") (pinfunction "1_1") (pintype "passive"))
      (node (ref "C6") (pin "1") (pinfunction "1_1") (pintype "passive"))
      (node (ref "C9") (pin "+") (pinfunction "+_+") (pintype "passive"))
      (node (ref "J4") (pin "1") (pinfunction "S_1") (pintype "passive"))
      (node (ref "JP1") (pin "2") (pinfunction "1_2") (pintype "passive"))
      (node (ref "L1") (pin "P$1") (pinfunction "1_P$1") (pintype "passive"))
      (node (ref "L4") (pin "2") (pinfunction "2_2") (pintype "passive"))
      (node (ref "R12") (pin "2") (pinfunction "2_2") (pintype "passive"))
      (node (ref "R13") (pin "2") (pinfunction "2_2") (pintype "passive"))
      (node (ref "U1") (pin "3") (pinfunction "IN_3") (pintype "power_in"))
      (node (ref "U3") (pin "P10") (pinfunction "VBAT_P10") (pintype "output"))
      (node (ref "U3") (pin "P9") (pinfunction "VSEN_P9") (pintype "input"))
      (node (ref "U5") (pin "1") (pinfunction "CE_1") (pintype "input"))
      (node (ref "U5") (pin "5") (pinfunction "VIN_5") (pintype "power_in"))
      (node (ref "U6") (pin "6") (pinfunction "VIN_6") (pintype "power_in"))
      (node (ref "U7") (pin "10") (pinfunction "BAT_10") (pintype "bidirectional"))
    )
    (net (code "85") (name "unconnected-(P1-SHUNT-Pad2)") (class "Default")
      (node (ref "P1") (pin "2") (pinfunction "SHUNT_2") (pintype "power_in"))
    )
    (net (code "86") (name "unconnected-(P2-SHUNT-Pad2)") (class "Default")
      (node (ref "P2") (pin "2") (pinfunction "SHUNT_2") (pintype "power_in"))
    )
    (net (code "87") (name "unconnected-(U2-AIN0-Pad2)") (class "Default")
      (node (ref "U2") (pin "2") (pinfunction "AIN0_2") (pintype "input"))
    )
    (net (code "88") (name "unconnected-(U4-I{slash}O-Pad3)") (class "Default")
      (node (ref "U4") (pin "3") (pinfunction "I/O_3") (pintype "bidirectional"))
    )
    (net (code "89") (name "unconnected-(U4-I{slash}O_3-Pad4)") (class "Default")
      (node (ref "U4") (pin "4") (pinfunction "I/O_3_4") (pintype "bidirectional"))
    )
    (net (code "90") (name "unconnected-(U5-NC-Pad2)") (class "Default")
      (node (ref "U5") (pin "2") (pinfunction "NC_2") (pintype "no_connect"))
    )
    (net (code "91") (name "unconnected-(U8-NC-Pad6)") (class "Default")
      (node (ref "U8") (pin "6") (pinfunction "NC_6") (pintype "no_connect"))
    )
    (net (code "92") (name "unconnected-(U8-NC_2-Pad7)") (class "Default")
      (node (ref "U8") (pin "7") (pinfunction "NC_2_7") (pintype "no_connect"))
    )
    (net (code "93") (name "unconnected-(U8-NC_3-Pad13)") (class "Default")
      (node (ref "U8") (pin "13") (pinfunction "NC_3_13") (pintype "no_connect"))
    )
    (net (code "94") (name "unconnected-(U8-NC_4-Pad12)") (class "Default")
      (node (ref "U8") (pin "12") (pinfunction "NC_4_12") (pintype "no_connect"))
    )
    (net (code "95") (name "unconnected-(U8-NC_5-Pad16)") (class "Default")
      (node (ref "U8") (pin "16") (pinfunction "NC_5_16") (pintype "no_connect"))
    )
    (net (code "96") (name "unconnected-(U8-NC_6-Pad8)") (class "Default")
      (node (ref "U8") (pin "8") (pinfunction "NC_6_8") (pintype "no_connect"))
    )
    (net (code "97") (name "unconnected-(U8-NC_7-Pad15)") (class "Default")
      (node (ref "U8") (pin "15") (pinfunction "NC_7_15") (pintype "no_connect"))
    )
    (net (code "98") (name "unconnected-(U8-SQW(1)-Pad4)") (class "Default")
      (node (ref "U8") (pin "4") (pinfunction "SQW(1)_4") (pintype "input"))
    )
    (net (code "99") (name "unconnected-(U9-INT2-Pad9)") (class "Default")
      (node (ref "U9") (pin "9") (pinfunction "INT2_9") (pintype "output"))
    )
    (net (code "100") (name "unconnected-(U9-NC_3-Pad3)") (class "Default")
      (node (ref "U9") (pin "3") (pinfunction "NC_3_3") (pintype "no_connect"))
    )
    (net (code "101") (name "unconnected-(U9-NC_8-Pad8)") (class "Default")
      (node (ref "U9") (pin "8") (pinfunction "NC_8_8") (pintype "no_connect"))
    )
    (net (code "102") (name "unconnected-(U9-NC_13-Pad13)") (class "Default")
      (node (ref "U9") (pin "13") (pinfunction "NC_13_13") (pintype "no_connect"))
    )
    (net (code "103") (name "unconnected-(U9-NC_16-Pad16)") (class "Default")
      (node (ref "U9") (pin "16") (pinfunction "NC_16_16") (pintype "no_connect"))
    )
    (net (code "104") (name "unconnected-(U10-GPIO0{slash}~{DSRB}-Pad18)") (class "Default")
      (node (ref "U10") (pin "18") (pinfunction "GPIO0/~{DSRB}_18") (pintype "bidirectional"))
    )
    (net (code "105") (name "unconnected-(U10-GPIO1{slash}~{DTRB}-Pad19)") (class "Default")
      (node (ref "U10") (pin "19") (pinfunction "GPIO1/~{DTRB}_19") (pintype "bidirectional"))
    )
    (net (code "106") (name "unconnected-(U10-GPIO2{slash}~{CDB}-Pad20)") (class "Default")
      (node (ref "U10") (pin "20") (pinfunction "GPIO2/~{CDB}_20") (pintype "bidirectional"))
    )
    (net (code "107") (name "unconnected-(U10-GPIO3{slash}~{RIB}-Pad21)") (class "Default")
      (node (ref "U10") (pin "21") (pinfunction "GPIO3/~{RIB}_21") (pintype "bidirectional"))
    )
    (net (code "108") (name "unconnected-(U10-GPIO4{slash}~{DSRA}-Pad25)") (class "Default")
      (node (ref "U10") (pin "25") (pinfunction "GPIO4/~{DSRA}_25") (pintype "bidirectional"))
    )
    (net (code "109") (name "unconnected-(U10-GPIO5{slash}~{DTRA}-Pad26)") (class "Default")
      (node (ref "U10") (pin "26") (pinfunction "GPIO5/~{DTRA}_26") (pintype "bidirectional"))
    )
    (net (code "110") (name "unconnected-(U10-GPIO6{slash}~{CDA}-Pad27)") (class "Default")
      (node (ref "U10") (pin "27") (pinfunction "GPIO6/~{CDA}_27") (pintype "bidirectional"))
    )
    (net (code "111") (name "unconnected-(U10-GPIO7{slash}~{RIA}-Pad28)") (class "Default")
      (node (ref "U10") (pin "28") (pinfunction "GPIO7/~{RIA}_28") (pintype "bidirectional"))
    )
    (net (code "112") (name "unconnected-(U10-N.C-Pad12)") (class "Default")
      (node (ref "U10") (pin "12") (pinfunction "N.C_12") (pintype "no_connect"))
    )
    (net (code "113") (name "unconnected-(U12-PIO0_1{slash}CLKOUT{slash}CT32B0_MAT2-Pad4)") (class "Default")
      (node (ref "U12") (pin "4") (pinfunction "PIO0_1/CLKOUT/CT32B0_MAT2_4") (pintype "bidirectional"))
    )
    (net (code "114") (name "unconnected-(U12-PIO0_9{slash}MOSI0{slash}CT16B0_MAT1-Pad28)") (class "Default")
      (node (ref "U12") (pin "28") (pinfunction "PIO0_9/MOSI0/CT16B0_MAT1_28") (pintype "bidirectional"))
    )
    (net (code "115") (name "unconnected-(U12-PIO0_18{slash}RXD{slash}CT32B0_MAT0-Pad46)") (class "Default")
      (node (ref "U12") (pin "46") (pinfunction "PIO0_18/RXD/CT32B0_MAT0_46") (pintype "bidirectional"))
    )
    (net (code "116") (name "unconnected-(U12-PIO0_19{slash}TXD{slash}CT32B0_MAT1-Pad47)") (class "Default")
      (node (ref "U12") (pin "47") (pinfunction "PIO0_19/TXD/CT32B0_MAT1_47") (pintype "bidirectional"))
    )
    (net (code "117") (name "unconnected-(U12-PIO0_21{slash}CT16B1_MAT0{slash}MOSI1-Pad17)") (class "Default")
      (node (ref "U12") (pin "17") (pinfunction "PIO0_21/CT16B1_MAT0/MOSI1_17") (pintype "bidirectional"))
    )
    (net (code "118") (name "unconnected-(U12-PIO0_22{slash}AD6{slash}CT16B1_MAT1{slash}MISO1-Pad30)") (class "Default")
      (node (ref "U12") (pin "30") (pinfunction "PIO0_22/AD6/CT16B1_MAT1/MISO1_30") (pintype "bidirectional"))
    )
    (net (code "119") (name "unconnected-(U12-PIO0_23{slash}AD7-Pad18)") (class "Default")
      (node (ref "U12") (pin "18") (pinfunction "PIO0_23/AD7_18") (pintype "bidirectional"))
    )
    (net (code "120") (name "unconnected-(U12-PIO1_16{slash}~{RI}{slash}CT16B0_CAP0-Pad48)") (class "Default")
      (node (ref "U12") (pin "48") (pinfunction "PIO1_16/~{RI}/CT16B0_CAP0_48") (pintype "bidirectional"))
    )
    (net (code "121") (name "unconnected-(U12-PIO1_19{slash}~{DTR}{slash}SSEL-Pad2)") (class "Default")
      (node (ref "U12") (pin "2") (pinfunction "PIO1_19/~{DTR}/SSEL_2") (pintype "bidirectional"))
    )
    (net (code "122") (name "unconnected-(U12-PIO1_20{slash}~{DSR}{slash}SCK1-Pad13)") (class "Default")
      (node (ref "U12") (pin "13") (pinfunction "PIO1_20/~{DSR}/SCK1_13") (pintype "bidirectional"))
    )
    (net (code "123") (name "unconnected-(U12-PIO1_21{slash}DCD{slash}MISO1-Pad26)") (class "Default")
      (node (ref "U12") (pin "26") (pinfunction "PIO1_21/DCD/MISO1_26") (pintype "bidirectional"))
    )
    (net (code "124") (name "unconnected-(U12-PIO1_22{slash}RI{slash}MOSI1-Pad38)") (class "Default")
      (node (ref "U12") (pin "38") (pinfunction "PIO1_22/RI/MOSI1_38") (pintype "bidirectional"))
    )
    (net (code "125") (name "unconnected-(U12-PIO1_23{slash}CT16B1_MAT1{slash}SSEL1-Pad42)") (class "Default")
      (node (ref "U12") (pin "42") (pinfunction "PIO1_23/CT16B1_MAT1/SSEL1_42") (pintype "bidirectional"))
    )
    (net (code "126") (name "unconnected-(U12-PIO1_24{slash}CT32B0_MAT0-Pad21)") (class "Default")
      (node (ref "U12") (pin "21") (pinfunction "PIO1_24/CT32B0_MAT0_21") (pintype "bidirectional"))
    )
    (net (code "127") (name "unconnected-(U12-PIO1_25{slash}CT32B0_MAT1-Pad1)") (class "Default")
      (node (ref "U12") (pin "1") (pinfunction "PIO1_25/CT32B0_MAT1_1") (pintype "bidirectional"))
    )
    (net (code "128") (name "unconnected-(U12-PIO1_29{slash}SCK0{slash}CT32B0_CAP1-Pad31)") (class "Default")
      (node (ref "U12") (pin "31") (pinfunction "PIO1_29/SCK0/CT32B0_CAP1_31") (pintype "bidirectional"))
    )
    (net (code "129") (name "unconnected-(USB0-ID-PadP4)") (class "Default")
      (node (ref "USB0") (pin "P4") (pinfunction "ID_P4") (pintype "bidirectional"))
    )
    (net (code "130") (name "unconnected-(USB2A-D+-PadUSB1-3)") (class "Default")
      (node (ref "USB2") (pin "USB1-3") (pinfunction "D+_USB1-3") (pintype "bidirectional"))
    )
    (net (code "131") (name "unconnected-(USB2A-D--PadUSB1-2)") (class "Default")
      (node (ref "USB2") (pin "USB1-2") (pinfunction "D-_USB1-2") (pintype "bidirectional"))
    )
    (net (code "132") (name "unconnected-(USB2B-D+-PadUSB2-3)") (class "Default")
      (node (ref "USB2") (pin "USB2-3") (pinfunction "D+_USB2-3") (pintype "bidirectional"))
    )
    (net (code "133") (name "unconnected-(USB2B-D--PadUSB2-2)") (class "Default")
      (node (ref "USB2") (pin "USB2-2") (pinfunction "D-_USB2-2") (pintype "bidirectional"))
    )
  )
)
